# Eurocard_VME_6U_P1.net
KiCad netlist of a schematic drawn in Altium Designer
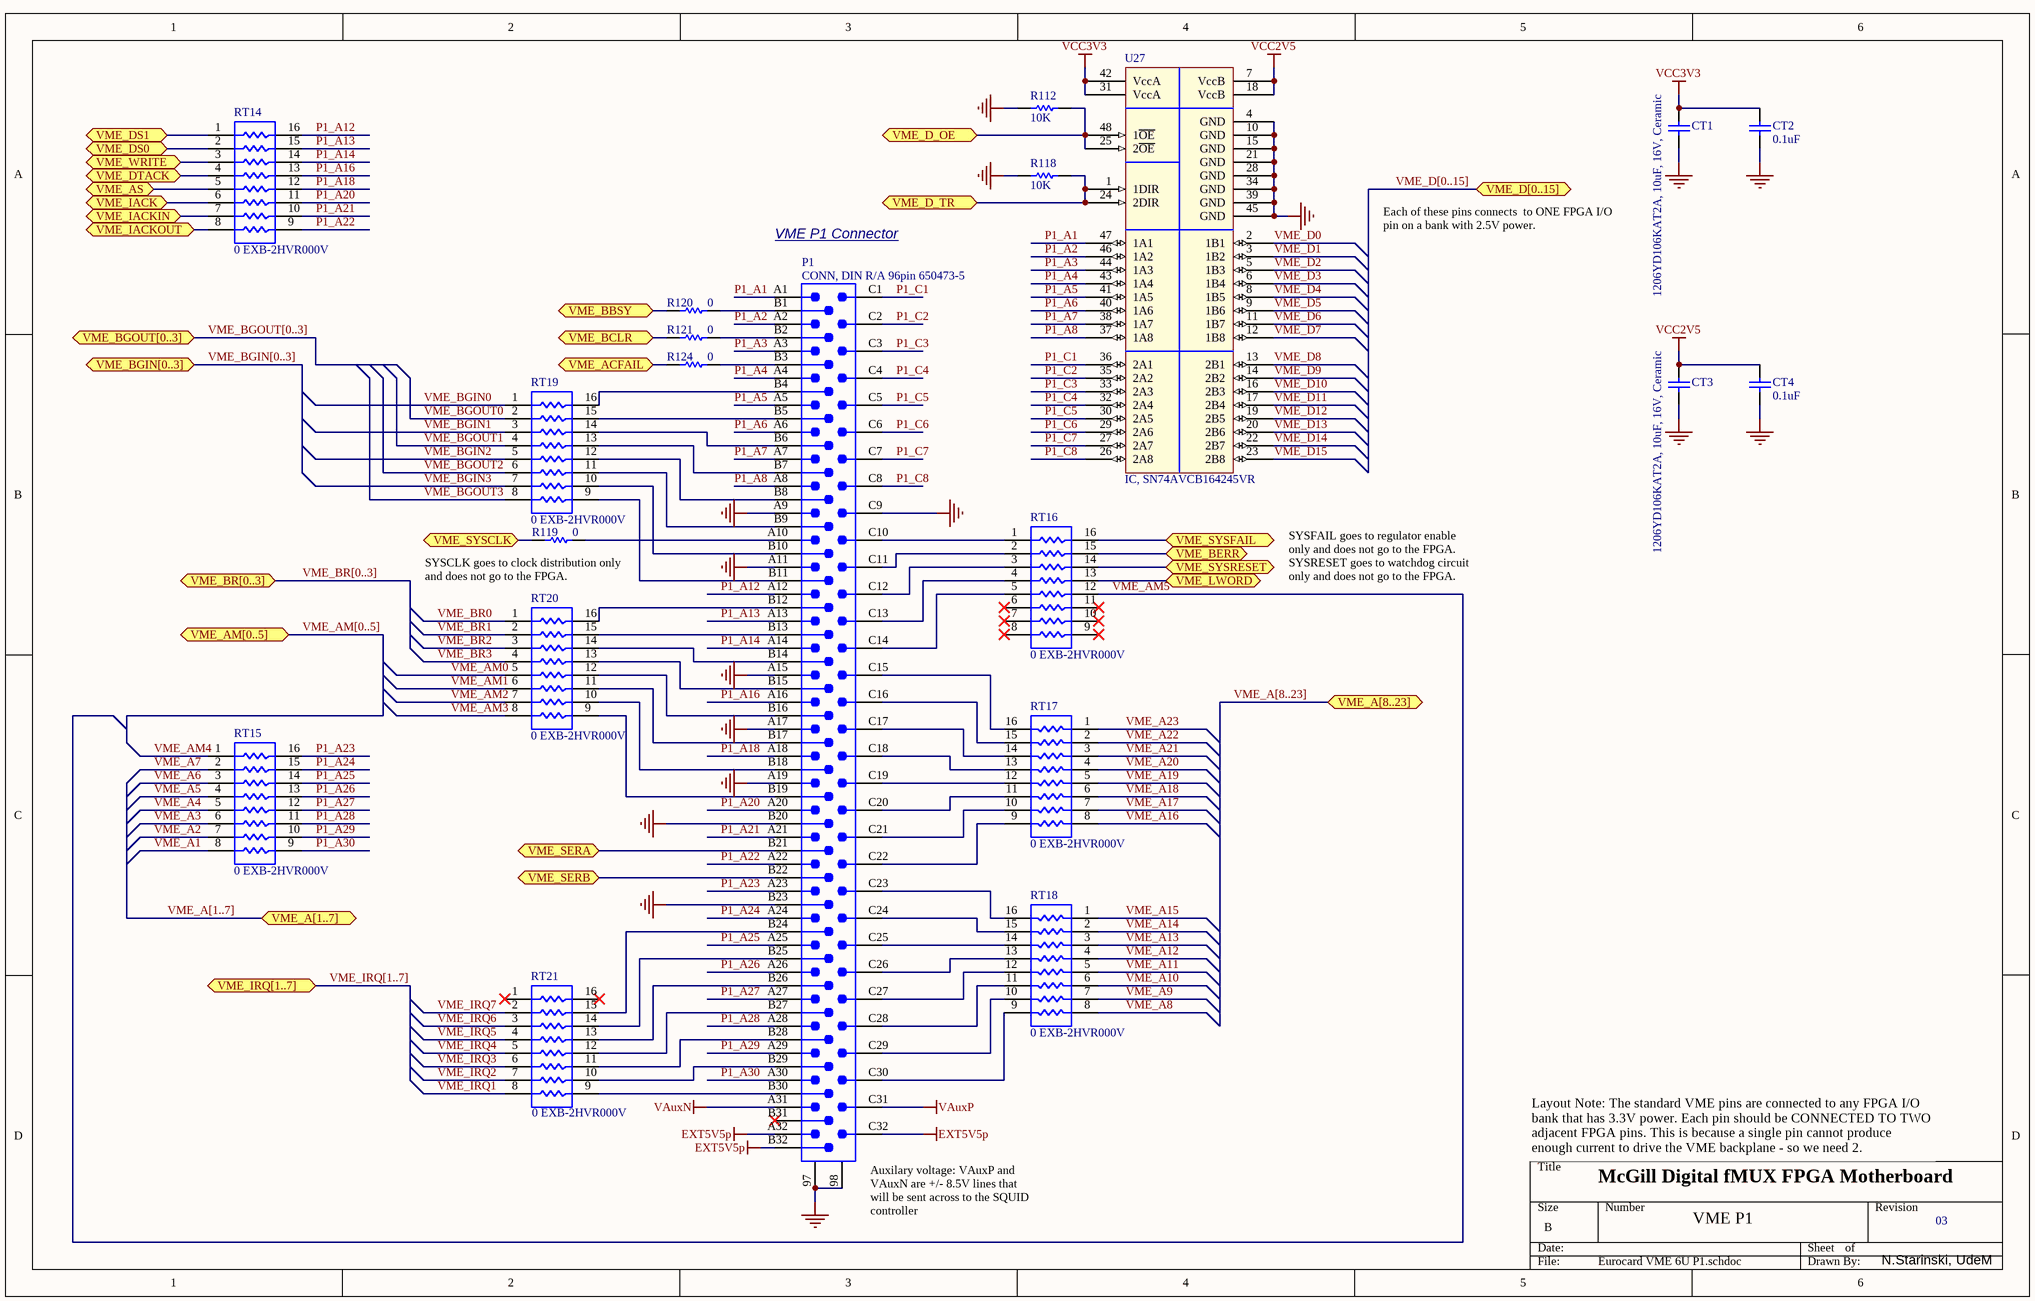
[diagram p0: Eurocard VME 6U P1.schdoc]

(export (version "E")
  (design (tool "Eeschema 10.0.6"))
  (components
    (comp (ref "CT1")
      (value "1206YD106KAT2A, 10uF, 16V, Ceramic")
      (footprint "CC3225-1210")
      (description "CAP POL 1206YD106KAT2A")
      (fields (field (name "PUBLISHER") "Altium Limited"))
      (libsource (lib "Miscellaneous Devices") (part "Cap Semi"))
    )
    (comp (ref "CT2")
      (value "0.1uF")
      (footprint "CC1608-0603")
      (description "Capacitor (Semiconductor SIM Model)")
      (fields (field (name "PUBLISHER") "Altium Limited"))
      (libsource (lib "Miscellaneous Devices") (part "Cap Semi"))
    )
    (comp (ref "CT3")
      (value "1206YD106KAT2A, 10uF, 16V, Ceramic")
      (footprint "CC3225-1210")
      (description "CAP POL 1206YD106KAT2A")
      (fields (field (name "PUBLISHER") "Altium Limited"))
      (libsource (lib "Miscellaneous Devices") (part "Cap Semi"))
    )
    (comp (ref "CT4")
      (value "0.1uF")
      (footprint "CC1608-0603")
      (description "Capacitor (Semiconductor SIM Model)")
      (fields (field (name "PUBLISHER") "Altium Limited"))
      (libsource (lib "Miscellaneous Devices") (part "Cap Semi"))
    )
    (comp (ref "P1")
      (value "CONN, DIN R/A 96pin 650473-5")
      (footprint "CNVME96")
      (description "96-Pin Connector (3x32 2.54mm grid)")
      (libsource (lib "*") (part "CNVME96"))
    )
    (comp (ref "R112")
      (value "10K")
      (footprint "CR1608-0603")
      (description "Resistor 0603")
      (fields (field (name "PUBLISHER") "Altium Limited"))
      (libsource (lib "Miscellaneous Devices") (part "Res Semi"))
    )
    (comp (ref "R118")
      (value "10K")
      (footprint "CR1608-0603")
      (description "Resistor 0603")
      (fields (field (name "PUBLISHER") "Altium Limited"))
      (libsource (lib "Miscellaneous Devices") (part "Res Semi"))
    )
    (comp (ref "R119")
      (value "0")
      (footprint "CR1608-0603")
      (description "Resistor 0603")
      (fields (field (name "PUBLISHER") "Altium Limited"))
      (libsource (lib "Miscellaneous Devices") (part "Res Semi"))
    )
    (comp (ref "R120")
      (value "0")
      (footprint "CR1608-0603")
      (description "Resistor 0603")
      (fields (field (name "PUBLISHER") "Altium Limited"))
      (libsource (lib "Miscellaneous Devices") (part "Res Semi"))
    )
    (comp (ref "R121")
      (value "0")
      (footprint "CR1608-0603")
      (description "Resistor 0603")
      (fields (field (name "PUBLISHER") "Altium Limited"))
      (libsource (lib "Miscellaneous Devices") (part "Res Semi"))
    )
    (comp (ref "R124")
      (value "0")
      (footprint "CR1608-0603")
      (description "Resistor 0603")
      (fields (field (name "PUBLISHER") "Altium Limited"))
      (libsource (lib "Miscellaneous Devices") (part "Res Semi"))
    )
    (comp (ref "RT14")
      (value "0 EXB-2HVR000V")
      (footprint "0402_Array_2HV")
      (description "Isolated Resistor Network")
      (fields (field (name "PUBLISHER") "Altium Limited"))
      (libsource (lib "Miscellaneous Devices 02") (part "Res Pack3"))
    )
    (comp (ref "RT15")
      (value "0 EXB-2HVR000V")
      (footprint "0402_Array_2HV")
      (description "Isolated Resistor Network")
      (fields (field (name "PUBLISHER") "Altium Limited"))
      (libsource (lib "Miscellaneous Devices 02") (part "Res Pack3"))
    )
    (comp (ref "RT16")
      (value "0 EXB-2HVR000V")
      (footprint "0402_Array_2HV")
      (description "Isolated Resistor Network")
      (fields (field (name "PUBLISHER") "Altium Limited"))
      (libsource (lib "Miscellaneous Devices 02") (part "Res Pack3"))
    )
    (comp (ref "RT17")
      (value "0 EXB-2HVR000V")
      (footprint "0402_Array_2HV")
      (description "Isolated Resistor Network")
      (fields (field (name "PUBLISHER") "Altium Limited"))
      (libsource (lib "Miscellaneous Devices 02") (part "Res Pack3"))
    )
    (comp (ref "RT18")
      (value "0 EXB-2HVR000V")
      (description "Isolated Resistor Network")
      (fields (field (name "PUBLISHER") "Altium Limited"))
      (libsource (lib "Miscellaneous Devices 02") (part "Res Pack3"))
    )
    (comp (ref "RT19")
      (value "0 EXB-2HVR000V")
      (footprint "0402_Array_2HV")
      (description "Isolated Resistor Network")
      (fields (field (name "PUBLISHER") "Altium Limited"))
      (libsource (lib "Miscellaneous Devices 02") (part "Res Pack3"))
    )
    (comp (ref "RT20")
      (value "0 EXB-2HVR000V")
      (footprint "0402_Array_2HV")
      (description "Isolated Resistor Network")
      (fields (field (name "PUBLISHER") "Altium Limited"))
      (libsource (lib "Miscellaneous Devices 02") (part "Res Pack3"))
    )
    (comp (ref "RT21")
      (value "0 EXB-2HVR000V")
      (footprint "0402_Array_2HV")
      (description "Isolated Resistor Network")
      (fields (field (name "PUBLISHER") "Altium Limited"))
      (libsource (lib "Miscellaneous Devices 02") (part "Res Pack3"))
    )
    (comp (ref "U27")
      (value "IC, SN74AVCB164245VR")
      (footprint "DGV048")
      (description "16-Bit Dual-Supply Bus Transceiver with CVT and 3-state")
      (libsource (lib "TI Interface Line Transceiver") (part "SN74AVCB164245"))
    )
  )
  (nets
    (net (code "1") (name "/P1_A1") (class "Default")
      (node (ref "P1") (pin "A1") (pinfunction "A1_A1") (pintype "passive"))
      (node (ref "U27") (pin "47") (pinfunction "1A1_47") (pintype "bidirectional"))
    )
    (net (code "2") (name "/P1_A2") (class "Default")
      (node (ref "P1") (pin "A2") (pinfunction "A2_A2") (pintype "passive"))
      (node (ref "U27") (pin "46") (pinfunction "1A2_46") (pintype "bidirectional"))
    )
    (net (code "3") (name "/P1_A3") (class "Default")
      (node (ref "P1") (pin "A3") (pinfunction "A3_A3") (pintype "passive"))
      (node (ref "U27") (pin "44") (pinfunction "1A3_44") (pintype "bidirectional"))
    )
    (net (code "4") (name "/P1_A4") (class "Default")
      (node (ref "P1") (pin "A4") (pinfunction "A4_A4") (pintype "passive"))
      (node (ref "U27") (pin "43") (pinfunction "1A4_43") (pintype "bidirectional"))
    )
    (net (code "5") (name "/P1_A5") (class "Default")
      (node (ref "P1") (pin "A5") (pinfunction "A5_A5") (pintype "passive"))
      (node (ref "U27") (pin "41") (pinfunction "1A5_41") (pintype "bidirectional"))
    )
    (net (code "6") (name "/P1_A6") (class "Default")
      (node (ref "P1") (pin "A6") (pinfunction "A6_A6") (pintype "passive"))
      (node (ref "U27") (pin "40") (pinfunction "1A6_40") (pintype "bidirectional"))
    )
    (net (code "7") (name "/P1_A7") (class "Default")
      (node (ref "P1") (pin "A7") (pinfunction "A7_A7") (pintype "passive"))
      (node (ref "U27") (pin "38") (pinfunction "1A7_38") (pintype "bidirectional"))
    )
    (net (code "8") (name "/P1_A8") (class "Default")
      (node (ref "P1") (pin "A8") (pinfunction "A8_A8") (pintype "passive"))
      (node (ref "U27") (pin "37") (pinfunction "1A8_37") (pintype "bidirectional"))
    )
    (net (code "9") (name "/P1_A12") (class "Default")
      (node (ref "P1") (pin "A12") (pinfunction "A12_A12") (pintype "passive"))
      (node (ref "RT14") (pin "16") (pinfunction "16_16") (pintype "passive"))
    )
    (net (code "10") (name "/P1_A13") (class "Default")
      (node (ref "P1") (pin "A13") (pinfunction "A13_A13") (pintype "passive"))
      (node (ref "RT14") (pin "15") (pinfunction "15_15") (pintype "passive"))
    )
    (net (code "11") (name "/P1_A14") (class "Default")
      (node (ref "P1") (pin "A14") (pinfunction "A14_A14") (pintype "passive"))
      (node (ref "RT14") (pin "14") (pinfunction "14_14") (pintype "passive"))
    )
    (net (code "12") (name "/P1_A16") (class "Default")
      (node (ref "P1") (pin "A16") (pinfunction "A16_A16") (pintype "passive"))
      (node (ref "RT14") (pin "13") (pinfunction "13_13") (pintype "passive"))
    )
    (net (code "13") (name "/P1_A18") (class "Default")
      (node (ref "P1") (pin "A18") (pinfunction "A18_A18") (pintype "passive"))
      (node (ref "RT14") (pin "12") (pinfunction "12_12") (pintype "passive"))
    )
    (net (code "14") (name "/P1_A20") (class "Default")
      (node (ref "P1") (pin "A20") (pinfunction "A20_A20") (pintype "passive"))
      (node (ref "RT14") (pin "11") (pinfunction "11_11") (pintype "passive"))
    )
    (net (code "15") (name "/P1_A21") (class "Default")
      (node (ref "P1") (pin "A21") (pinfunction "A21_A21") (pintype "passive"))
      (node (ref "RT14") (pin "10") (pinfunction "10_10") (pintype "passive"))
    )
    (net (code "16") (name "/P1_A22") (class "Default")
      (node (ref "P1") (pin "A22") (pinfunction "A22_A22") (pintype "passive"))
      (node (ref "RT14") (pin "9") (pinfunction "9_9") (pintype "passive"))
    )
    (net (code "17") (name "/P1_A23") (class "Default")
      (node (ref "P1") (pin "A23") (pinfunction "A23_A23") (pintype "passive"))
      (node (ref "RT15") (pin "16") (pinfunction "16_16") (pintype "passive"))
    )
    (net (code "18") (name "/P1_A24") (class "Default")
      (node (ref "P1") (pin "A24") (pinfunction "A24_A24") (pintype "passive"))
      (node (ref "RT15") (pin "15") (pinfunction "15_15") (pintype "passive"))
    )
    (net (code "19") (name "/P1_A25") (class "Default")
      (node (ref "P1") (pin "A25") (pinfunction "A25_A25") (pintype "passive"))
      (node (ref "RT15") (pin "14") (pinfunction "14_14") (pintype "passive"))
    )
    (net (code "20") (name "/P1_A26") (class "Default")
      (node (ref "P1") (pin "A26") (pinfunction "A26_A26") (pintype "passive"))
      (node (ref "RT15") (pin "13") (pinfunction "13_13") (pintype "passive"))
    )
    (net (code "21") (name "/P1_A27") (class "Default")
      (node (ref "P1") (pin "A27") (pinfunction "A27_A27") (pintype "passive"))
      (node (ref "RT15") (pin "12") (pinfunction "12_12") (pintype "passive"))
    )
    (net (code "22") (name "/P1_A28") (class "Default")
      (node (ref "P1") (pin "A28") (pinfunction "A28_A28") (pintype "passive"))
      (node (ref "RT15") (pin "11") (pinfunction "11_11") (pintype "passive"))
    )
    (net (code "23") (name "/P1_A29") (class "Default")
      (node (ref "P1") (pin "A29") (pinfunction "A29_A29") (pintype "passive"))
      (node (ref "RT15") (pin "10") (pinfunction "10_10") (pintype "passive"))
    )
    (net (code "24") (name "/P1_A30") (class "Default")
      (node (ref "P1") (pin "A30") (pinfunction "A30_A30") (pintype "passive"))
      (node (ref "RT15") (pin "9") (pinfunction "9_9") (pintype "passive"))
    )
    (net (code "25") (name "/P1_C1") (class "Default")
      (node (ref "P1") (pin "C1") (pinfunction "C1_C1") (pintype "passive"))
      (node (ref "U27") (pin "36") (pinfunction "2A1_36") (pintype "bidirectional"))
    )
    (net (code "26") (name "/P1_C2") (class "Default")
      (node (ref "P1") (pin "C2") (pinfunction "C2_C2") (pintype "passive"))
      (node (ref "U27") (pin "35") (pinfunction "2A2_35") (pintype "bidirectional"))
    )
    (net (code "27") (name "/P1_C3") (class "Default")
      (node (ref "P1") (pin "C3") (pinfunction "C3_C3") (pintype "passive"))
      (node (ref "U27") (pin "33") (pinfunction "2A3_33") (pintype "bidirectional"))
    )
    (net (code "28") (name "/P1_C4") (class "Default")
      (node (ref "P1") (pin "C4") (pinfunction "C4_C4") (pintype "passive"))
      (node (ref "U27") (pin "32") (pinfunction "2A4_32") (pintype "bidirectional"))
    )
    (net (code "29") (name "/P1_C5") (class "Default")
      (node (ref "P1") (pin "C5") (pinfunction "C5_C5") (pintype "passive"))
      (node (ref "U27") (pin "30") (pinfunction "2A5_30") (pintype "bidirectional"))
    )
    (net (code "30") (name "/P1_C6") (class "Default")
      (node (ref "P1") (pin "C6") (pinfunction "C6_C6") (pintype "passive"))
      (node (ref "U27") (pin "29") (pinfunction "2A6_29") (pintype "bidirectional"))
    )
    (net (code "31") (name "/P1_C7") (class "Default")
      (node (ref "P1") (pin "C7") (pinfunction "C7_C7") (pintype "passive"))
      (node (ref "U27") (pin "27") (pinfunction "2A7_27") (pintype "bidirectional"))
    )
    (net (code "32") (name "/P1_C8") (class "Default")
      (node (ref "P1") (pin "C8") (pinfunction "C8_C8") (pintype "passive"))
      (node (ref "U27") (pin "26") (pinfunction "2A8_26") (pintype "bidirectional"))
    )
    (net (code "33") (name "/VME_A1") (class "Default")
      (node (ref "RT15") (pin "8") (pinfunction "8_8") (pintype "passive"))
    )
    (net (code "34") (name "/VME_A2") (class "Default")
      (node (ref "RT15") (pin "7") (pinfunction "7_7") (pintype "passive"))
    )
    (net (code "35") (name "/VME_A3") (class "Default")
      (node (ref "RT15") (pin "6") (pinfunction "6_6") (pintype "passive"))
    )
    (net (code "36") (name "/VME_A4") (class "Default")
      (node (ref "RT15") (pin "5") (pinfunction "5_5") (pintype "passive"))
    )
    (net (code "37") (name "/VME_A5") (class "Default")
      (node (ref "RT15") (pin "4") (pinfunction "4_4") (pintype "passive"))
    )
    (net (code "38") (name "/VME_A6") (class "Default")
      (node (ref "RT15") (pin "3") (pinfunction "3_3") (pintype "passive"))
    )
    (net (code "39") (name "/VME_A7") (class "Default")
      (node (ref "RT15") (pin "2") (pinfunction "2_2") (pintype "passive"))
    )
    (net (code "40") (name "/VME_A8") (class "Default")
      (node (ref "RT18") (pin "8") (pinfunction "8_8") (pintype "passive"))
    )
    (net (code "41") (name "/VME_A9") (class "Default")
      (node (ref "RT18") (pin "7") (pinfunction "7_7") (pintype "passive"))
    )
    (net (code "42") (name "/VME_A10") (class "Default")
      (node (ref "RT18") (pin "6") (pinfunction "6_6") (pintype "passive"))
    )
    (net (code "43") (name "/VME_A11") (class "Default")
      (node (ref "RT18") (pin "5") (pinfunction "5_5") (pintype "passive"))
    )
    (net (code "44") (name "/VME_A12") (class "Default")
      (node (ref "RT18") (pin "4") (pinfunction "4_4") (pintype "passive"))
    )
    (net (code "45") (name "/VME_A13") (class "Default")
      (node (ref "RT18") (pin "3") (pinfunction "3_3") (pintype "passive"))
    )
    (net (code "46") (name "/VME_A14") (class "Default")
      (node (ref "RT18") (pin "2") (pinfunction "2_2") (pintype "passive"))
    )
    (net (code "47") (name "/VME_A15") (class "Default")
      (node (ref "RT18") (pin "1") (pinfunction "1_1") (pintype "passive"))
    )
    (net (code "48") (name "/VME_A16") (class "Default")
      (node (ref "RT17") (pin "8") (pinfunction "8_8") (pintype "passive"))
    )
    (net (code "49") (name "/VME_A17") (class "Default")
      (node (ref "RT17") (pin "7") (pinfunction "7_7") (pintype "passive"))
    )
    (net (code "50") (name "/VME_A18") (class "Default")
      (node (ref "RT17") (pin "6") (pinfunction "6_6") (pintype "passive"))
    )
    (net (code "51") (name "/VME_A19") (class "Default")
      (node (ref "RT17") (pin "5") (pinfunction "5_5") (pintype "passive"))
    )
    (net (code "52") (name "/VME_A20") (class "Default")
      (node (ref "RT17") (pin "4") (pinfunction "4_4") (pintype "passive"))
    )
    (net (code "53") (name "/VME_A21") (class "Default")
      (node (ref "RT17") (pin "3") (pinfunction "3_3") (pintype "passive"))
    )
    (net (code "54") (name "/VME_A22") (class "Default")
      (node (ref "RT17") (pin "2") (pinfunction "2_2") (pintype "passive"))
    )
    (net (code "55") (name "/VME_A23") (class "Default")
      (node (ref "RT17") (pin "1") (pinfunction "1_1") (pintype "passive"))
    )
    (net (code "56") (name "/VME_ACFAIL") (class "Default")
      (node (ref "R124") (pin "1") (pinfunction "1_1") (pintype "passive"))
    )
    (net (code "57") (name "/VME_AM0") (class "Default")
      (node (ref "RT20") (pin "5") (pinfunction "5_5") (pintype "passive"))
    )
    (net (code "58") (name "/VME_AM1") (class "Default")
      (node (ref "RT20") (pin "6") (pinfunction "6_6") (pintype "passive"))
    )
    (net (code "59") (name "/VME_AM2") (class "Default")
      (node (ref "RT20") (pin "7") (pinfunction "7_7") (pintype "passive"))
    )
    (net (code "60") (name "/VME_AM3") (class "Default")
      (node (ref "RT20") (pin "8") (pinfunction "8_8") (pintype "passive"))
    )
    (net (code "61") (name "/VME_AM4") (class "Default")
      (node (ref "RT15") (pin "1") (pinfunction "1_1") (pintype "passive"))
    )
    (net (code "62") (name "/VME_AM5") (class "Default")
      (node (ref "RT16") (pin "12") (pinfunction "12_12") (pintype "passive"))
    )
    (net (code "64") (name "/VME_AS") (class "Default")
      (node (ref "RT14") (pin "5") (pinfunction "5_5") (pintype "passive"))
    )
    (net (code "67") (name "/VME_BBSY") (class "Default")
      (node (ref "R120") (pin "1") (pinfunction "1_1") (pintype "passive"))
    )
    (net (code "68") (name "/VME_BCLR") (class "Default")
      (node (ref "R121") (pin "1") (pinfunction "1_1") (pintype "passive"))
    )
    (net (code "69") (name "/VME_BERR") (class "Default")
      (node (ref "RT16") (pin "15") (pinfunction "15_15") (pintype "passive"))
    )
    (net (code "70") (name "/VME_BGIN0") (class "Default")
      (node (ref "RT19") (pin "1") (pinfunction "1_1") (pintype "passive"))
    )
    (net (code "71") (name "/VME_BGIN1") (class "Default")
      (node (ref "RT19") (pin "3") (pinfunction "3_3") (pintype "passive"))
    )
    (net (code "72") (name "/VME_BGIN2") (class "Default")
      (node (ref "RT19") (pin "5") (pinfunction "5_5") (pintype "passive"))
    )
    (net (code "73") (name "/VME_BGIN3") (class "Default")
      (node (ref "RT19") (pin "7") (pinfunction "7_7") (pintype "passive"))
    )
    (net (code "75") (name "/VME_BGOUT0") (class "Default")
      (node (ref "RT19") (pin "2") (pinfunction "2_2") (pintype "passive"))
    )
    (net (code "76") (name "/VME_BGOUT1") (class "Default")
      (node (ref "RT19") (pin "4") (pinfunction "4_4") (pintype "passive"))
    )
    (net (code "77") (name "/VME_BGOUT2") (class "Default")
      (node (ref "RT19") (pin "6") (pinfunction "6_6") (pintype "passive"))
    )
    (net (code "78") (name "/VME_BGOUT3") (class "Default")
      (node (ref "RT19") (pin "8") (pinfunction "8_8") (pintype "passive"))
    )
    (net (code "80") (name "/VME_BR0") (class "Default")
      (node (ref "RT20") (pin "1") (pinfunction "1_1") (pintype "passive"))
    )
    (net (code "81") (name "/VME_BR1") (class "Default")
      (node (ref "RT20") (pin "2") (pinfunction "2_2") (pintype "passive"))
    )
    (net (code "82") (name "/VME_BR2") (class "Default")
      (node (ref "RT20") (pin "3") (pinfunction "3_3") (pintype "passive"))
    )
    (net (code "83") (name "/VME_BR3") (class "Default")
      (node (ref "RT20") (pin "4") (pinfunction "4_4") (pintype "passive"))
    )
    (net (code "85") (name "/VME_D0") (class "Default")
      (node (ref "U27") (pin "2") (pinfunction "1B1_2") (pintype "bidirectional"))
    )
    (net (code "86") (name "/VME_D1") (class "Default")
      (node (ref "U27") (pin "3") (pinfunction "1B2_3") (pintype "bidirectional"))
    )
    (net (code "87") (name "/VME_D2") (class "Default")
      (node (ref "U27") (pin "5") (pinfunction "1B3_5") (pintype "bidirectional"))
    )
    (net (code "88") (name "/VME_D3") (class "Default")
      (node (ref "U27") (pin "6") (pinfunction "1B4_6") (pintype "bidirectional"))
    )
    (net (code "89") (name "/VME_D4") (class "Default")
      (node (ref "U27") (pin "8") (pinfunction "1B5_8") (pintype "bidirectional"))
    )
    (net (code "90") (name "/VME_D5") (class "Default")
      (node (ref "U27") (pin "9") (pinfunction "1B6_9") (pintype "bidirectional"))
    )
    (net (code "91") (name "/VME_D6") (class "Default")
      (node (ref "U27") (pin "11") (pinfunction "1B7_11") (pintype "bidirectional"))
    )
    (net (code "92") (name "/VME_D7") (class "Default")
      (node (ref "U27") (pin "12") (pinfunction "1B8_12") (pintype "bidirectional"))
    )
    (net (code "93") (name "/VME_D8") (class "Default")
      (node (ref "U27") (pin "13") (pinfunction "2B1_13") (pintype "bidirectional"))
    )
    (net (code "94") (name "/VME_D9") (class "Default")
      (node (ref "U27") (pin "14") (pinfunction "2B2_14") (pintype "bidirectional"))
    )
    (net (code "95") (name "/VME_D10") (class "Default")
      (node (ref "U27") (pin "16") (pinfunction "2B3_16") (pintype "bidirectional"))
    )
    (net (code "96") (name "/VME_D11") (class "Default")
      (node (ref "U27") (pin "17") (pinfunction "2B4_17") (pintype "bidirectional"))
    )
    (net (code "97") (name "/VME_D12") (class "Default")
      (node (ref "U27") (pin "19") (pinfunction "2B5_19") (pintype "bidirectional"))
    )
    (net (code "98") (name "/VME_D13") (class "Default")
      (node (ref "U27") (pin "20") (pinfunction "2B6_20") (pintype "bidirectional"))
    )
    (net (code "99") (name "/VME_D14") (class "Default")
      (node (ref "U27") (pin "22") (pinfunction "2B7_22") (pintype "bidirectional"))
    )
    (net (code "100") (name "/VME_D15") (class "Default")
      (node (ref "U27") (pin "23") (pinfunction "2B8_23") (pintype "bidirectional"))
    )
    (net (code "101") (name "/VME_DS0") (class "Default")
      (node (ref "RT14") (pin "2") (pinfunction "2_2") (pintype "passive"))
    )
    (net (code "102") (name "/VME_DS1") (class "Default")
      (node (ref "RT14") (pin "1") (pinfunction "1_1") (pintype "passive"))
    )
    (net (code "103") (name "/VME_DTACK") (class "Default")
      (node (ref "RT14") (pin "4") (pinfunction "4_4") (pintype "passive"))
    )
    (net (code "105") (name "/VME_D_OE") (class "Default")
      (node (ref "R112") (pin "2") (pinfunction "2_2") (pintype "passive"))
      (node (ref "U27") (pin "25") (pinfunction "2~{OE}_25") (pintype "input"))
      (node (ref "U27") (pin "48") (pinfunction "1~{OE}_48") (pintype "input"))
    )
    (net (code "106") (name "/VME_D_TR") (class "Default")
      (node (ref "R118") (pin "2") (pinfunction "2_2") (pintype "passive"))
      (node (ref "U27") (pin "1") (pinfunction "1DIR_1") (pintype "input"))
      (node (ref "U27") (pin "24") (pinfunction "2DIR_24") (pintype "input"))
    )
    (net (code "107") (name "/VME_IACK") (class "Default")
      (node (ref "RT14") (pin "6") (pinfunction "6_6") (pintype "passive"))
    )
    (net (code "108") (name "/VME_IACKIN") (class "Default")
      (node (ref "RT14") (pin "7") (pinfunction "7_7") (pintype "passive"))
    )
    (net (code "109") (name "/VME_IACKOUT") (class "Default")
      (node (ref "RT14") (pin "8") (pinfunction "8_8") (pintype "passive"))
    )
    (net (code "110") (name "/VME_IRQ1") (class "Default")
      (node (ref "RT21") (pin "8") (pinfunction "8_8") (pintype "passive"))
    )
    (net (code "111") (name "/VME_IRQ2") (class "Default")
      (node (ref "RT21") (pin "7") (pinfunction "7_7") (pintype "passive"))
    )
    (net (code "112") (name "/VME_IRQ3") (class "Default")
      (node (ref "RT21") (pin "6") (pinfunction "6_6") (pintype "passive"))
    )
    (net (code "113") (name "/VME_IRQ4") (class "Default")
      (node (ref "RT21") (pin "5") (pinfunction "5_5") (pintype "passive"))
    )
    (net (code "114") (name "/VME_IRQ5") (class "Default")
      (node (ref "RT21") (pin "4") (pinfunction "4_4") (pintype "passive"))
    )
    (net (code "115") (name "/VME_IRQ6") (class "Default")
      (node (ref "RT21") (pin "3") (pinfunction "3_3") (pintype "passive"))
    )
    (net (code "116") (name "/VME_IRQ7") (class "Default")
      (node (ref "RT21") (pin "2") (pinfunction "2_2") (pintype "passive"))
    )
    (net (code "118") (name "/VME_LWORD") (class "Default")
      (node (ref "RT16") (pin "13") (pinfunction "13_13") (pintype "passive"))
    )
    (net (code "119") (name "/VME_SERA") (class "Default")
      (node (ref "P1") (pin "B21") (pinfunction "B21_B21") (pintype "passive"))
    )
    (net (code "120") (name "/VME_SERB") (class "Default")
      (node (ref "P1") (pin "B22") (pinfunction "B22_B22") (pintype "passive"))
    )
    (net (code "121") (name "/VME_SYSCLK") (class "Default")
      (node (ref "R119") (pin "1") (pinfunction "1_1") (pintype "passive"))
    )
    (net (code "122") (name "/VME_SYSFAIL") (class "Default")
      (node (ref "RT16") (pin "16") (pinfunction "16_16") (pintype "passive"))
    )
    (net (code "123") (name "/VME_SYSRESET") (class "Default")
      (node (ref "RT16") (pin "14") (pinfunction "14_14") (pintype "passive"))
    )
    (net (code "124") (name "/VME_WRITE") (class "Default")
      (node (ref "RT14") (pin "3") (pinfunction "3_3") (pintype "passive"))
    )
    (net (code "125") (name "EXT5V5p") (class "Default")
      (node (ref "P1") (pin "A32") (pinfunction "A32_A32") (pintype "passive"))
      (node (ref "P1") (pin "B32") (pinfunction "B32_B32") (pintype "passive"))
      (node (ref "P1") (pin "C32") (pinfunction "C32_C32") (pintype "passive"))
    )
    (net (code "126") (name "GND") (class "Default")
      (node (ref "CT1") (pin "2") (pinfunction "2_2") (pintype "passive"))
      (node (ref "CT2") (pin "2") (pinfunction "2_2") (pintype "passive"))
      (node (ref "CT3") (pin "2") (pinfunction "2_2") (pintype "passive"))
      (node (ref "CT4") (pin "2") (pinfunction "2_2") (pintype "passive"))
      (node (ref "P1") (pin "97") (pinfunction "97_97") (pintype "passive"))
      (node (ref "P1") (pin "98") (pinfunction "98_98") (pintype "passive"))
      (node (ref "P1") (pin "A11") (pinfunction "A11_A11") (pintype "passive"))
      (node (ref "P1") (pin "A15") (pinfunction "A15_A15") (pintype "passive"))
      (node (ref "P1") (pin "A17") (pinfunction "A17_A17") (pintype "passive"))
      (node (ref "P1") (pin "A19") (pinfunction "A19_A19") (pintype "passive"))
      (node (ref "P1") (pin "A9") (pinfunction "A9_A9") (pintype "passive"))
      (node (ref "P1") (pin "B20") (pinfunction "B20_B20") (pintype "passive"))
      (node (ref "P1") (pin "B23") (pinfunction "B23_B23") (pintype "passive"))
      (node (ref "P1") (pin "C9") (pinfunction "C9_C9") (pintype "passive"))
      (node (ref "R112") (pin "1") (pinfunction "1_1") (pintype "passive"))
      (node (ref "R118") (pin "1") (pinfunction "1_1") (pintype "passive"))
      (node (ref "U27") (pin "10") (pinfunction "GND_10") (pintype "power_in"))
      (node (ref "U27") (pin "15") (pinfunction "GND_15") (pintype "power_in"))
      (node (ref "U27") (pin "21") (pinfunction "GND_21") (pintype "power_in"))
      (node (ref "U27") (pin "28") (pinfunction "GND_28") (pintype "power_in"))
      (node (ref "U27") (pin "34") (pinfunction "GND_34") (pintype "power_in"))
      (node (ref "U27") (pin "39") (pinfunction "GND_39") (pintype "power_in"))
      (node (ref "U27") (pin "4") (pinfunction "GND_4") (pintype "power_in"))
      (node (ref "U27") (pin "45") (pinfunction "GND_45") (pintype "power_in"))
    )
    (net (code "127") (name "Net-(P1-PadA10)") (class "Default")
      (node (ref "P1") (pin "A10") (pinfunction "A10_A10") (pintype "passive"))
      (node (ref "R119") (pin "2") (pinfunction "2_2") (pintype "passive"))
    )
    (net (code "128") (name "Net-(P1-PadB1)") (class "Default")
      (node (ref "P1") (pin "B1") (pinfunction "B1_B1") (pintype "passive"))
      (node (ref "R120") (pin "2") (pinfunction "2_2") (pintype "passive"))
    )
    (net (code "129") (name "Net-(P1-PadB2)") (class "Default")
      (node (ref "P1") (pin "B2") (pinfunction "B2_B2") (pintype "passive"))
      (node (ref "R121") (pin "2") (pinfunction "2_2") (pintype "passive"))
    )
    (net (code "130") (name "Net-(P1-PadB3)") (class "Default")
      (node (ref "P1") (pin "B3") (pinfunction "B3_B3") (pintype "passive"))
      (node (ref "R124") (pin "2") (pinfunction "2_2") (pintype "passive"))
    )
    (net (code "131") (name "Net-(P1-PadB4)") (class "Default")
      (node (ref "P1") (pin "B4") (pinfunction "B4_B4") (pintype "passive"))
      (node (ref "RT19") (pin "16") (pinfunction "16_16") (pintype "passive"))
    )
    (net (code "132") (name "Net-(P1-PadB5)") (class "Default")
      (node (ref "P1") (pin "B5") (pinfunction "B5_B5") (pintype "passive"))
      (node (ref "RT19") (pin "15") (pinfunction "15_15") (pintype "passive"))
    )
    (net (code "133") (name "Net-(P1-PadB6)") (class "Default")
      (node (ref "P1") (pin "B6") (pinfunction "B6_B6") (pintype "passive"))
      (node (ref "RT19") (pin "14") (pinfunction "14_14") (pintype "passive"))
    )
    (net (code "134") (name "Net-(P1-PadB7)") (class "Default")
      (node (ref "P1") (pin "B7") (pinfunction "B7_B7") (pintype "passive"))
      (node (ref "RT19") (pin "13") (pinfunction "13_13") (pintype "passive"))
    )
    (net (code "135") (name "Net-(P1-PadB8)") (class "Default")
      (node (ref "P1") (pin "B8") (pinfunction "B8_B8") (pintype "passive"))
      (node (ref "RT19") (pin "12") (pinfunction "12_12") (pintype "passive"))
    )
    (net (code "136") (name "Net-(P1-PadB9)") (class "Default")
      (node (ref "P1") (pin "B9") (pinfunction "B9_B9") (pintype "passive"))
      (node (ref "RT19") (pin "11") (pinfunction "11_11") (pintype "passive"))
    )
    (net (code "137") (name "Net-(P1-PadB10)") (class "Default")
      (node (ref "P1") (pin "B10") (pinfunction "B10_B10") (pintype "passive"))
      (node (ref "RT19") (pin "10") (pinfunction "10_10") (pintype "passive"))
    )
    (net (code "138") (name "Net-(P1-PadB11)") (class "Default")
      (node (ref "P1") (pin "B11") (pinfunction "B11_B11") (pintype "passive"))
      (node (ref "RT19") (pin "9") (pinfunction "9_9") (pintype "passive"))
    )
    (net (code "139") (name "Net-(P1-PadB12)") (class "Default")
      (node (ref "P1") (pin "B12") (pinfunction "B12_B12") (pintype "passive"))
      (node (ref "RT20") (pin "16") (pinfunction "16_16") (pintype "passive"))
    )
    (net (code "140") (name "Net-(P1-PadB13)") (class "Default")
      (node (ref "P1") (pin "B13") (pinfunction "B13_B13") (pintype "passive"))
      (node (ref "RT20") (pin "15") (pinfunction "15_15") (pintype "passive"))
    )
    (net (code "141") (name "Net-(P1-PadB14)") (class "Default")
      (node (ref "P1") (pin "B14") (pinfunction "B14_B14") (pintype "passive"))
      (node (ref "RT20") (pin "14") (pinfunction "14_14") (pintype "passive"))
    )
    (net (code "142") (name "Net-(P1-PadB15)") (class "Default")
      (node (ref "P1") (pin "B15") (pinfunction "B15_B15") (pintype "passive"))
      (node (ref "RT20") (pin "13") (pinfunction "13_13") (pintype "passive"))
    )
    (net (code "143") (name "Net-(P1-PadB16)") (class "Default")
      (node (ref "P1") (pin "B16") (pinfunction "B16_B16") (pintype "passive"))
      (node (ref "RT20") (pin "12") (pinfunction "12_12") (pintype "passive"))
    )
    (net (code "144") (name "Net-(P1-PadB17)") (class "Default")
      (node (ref "P1") (pin "B17") (pinfunction "B17_B17") (pintype "passive"))
      (node (ref "RT20") (pin "11") (pinfunction "11_11") (pintype "passive"))
    )
    (net (code "145") (name "Net-(P1-PadB18)") (class "Default")
      (node (ref "P1") (pin "B18") (pinfunction "B18_B18") (pintype "passive"))
      (node (ref "RT20") (pin "10") (pinfunction "10_10") (pintype "passive"))
    )
    (net (code "146") (name "Net-(P1-PadB19)") (class "Default")
      (node (ref "P1") (pin "B19") (pinfunction "B19_B19") (pintype "passive"))
      (node (ref "RT20") (pin "9") (pinfunction "9_9") (pintype "passive"))
    )
    (net (code "147") (name "Net-(P1-PadB24)") (class "Default")
      (node (ref "P1") (pin "B24") (pinfunction "B24_B24") (pintype "passive"))
      (node (ref "RT21") (pin "15") (pinfunction "15_15") (pintype "passive"))
    )
    (net (code "148") (name "Net-(P1-PadB25)") (class "Default")
      (node (ref "P1") (pin "B25") (pinfunction "B25_B25") (pintype "passive"))
      (node (ref "RT21") (pin "14") (pinfunction "14_14") (pintype "passive"))
    )
    (net (code "149") (name "Net-(P1-PadB26)") (class "Default")
      (node (ref "P1") (pin "B26") (pinfunction "B26_B26") (pintype "passive"))
      (node (ref "RT21") (pin "13") (pinfunction "13_13") (pintype "passive"))
    )
    (net (code "150") (name "Net-(P1-PadB27)") (class "Default")
      (node (ref "P1") (pin "B27") (pinfunction "B27_B27") (pintype "passive"))
      (node (ref "RT21") (pin "12") (pinfunction "12_12") (pintype "passive"))
    )
    (net (code "151") (name "Net-(P1-PadB28)") (class "Default")
      (node (ref "P1") (pin "B28") (pinfunction "B28_B28") (pintype "passive"))
      (node (ref "RT21") (pin "11") (pinfunction "11_11") (pintype "passive"))
    )
    (net (code "152") (name "Net-(P1-PadB29)") (class "Default")
      (node (ref "P1") (pin "B29") (pinfunction "B29_B29") (pintype "passive"))
      (node (ref "RT21") (pin "10") (pinfunction "10_10") (pintype "passive"))
    )
    (net (code "153") (name "Net-(P1-PadB30)") (class "Default")
      (node (ref "P1") (pin "B30") (pinfunction "B30_B30") (pintype "passive"))
      (node (ref "RT21") (pin "9") (pinfunction "9_9") (pintype "passive"))
    )
    (net (code "154") (name "Net-(P1-PadC10)") (class "Default")
      (node (ref "P1") (pin "C10") (pinfunction "C10_C10") (pintype "passive"))
      (node (ref "RT16") (pin "1") (pinfunction "1_1") (pintype "passive"))
    )
    (net (code "155") (name "Net-(P1-PadC11)") (class "Default")
      (node (ref "P1") (pin "C11") (pinfunction "C11_C11") (pintype "passive"))
      (node (ref "RT16") (pin "2") (pinfunction "2_2") (pintype "passive"))
    )
    (net (code "156") (name "Net-(P1-PadC12)") (class "Default")
      (node (ref "P1") (pin "C12") (pinfunction "C12_C12") (pintype "passive"))
      (node (ref "RT16") (pin "3") (pinfunction "3_3") (pintype "passive"))
    )
    (net (code "157") (name "Net-(P1-PadC13)") (class "Default")
      (node (ref "P1") (pin "C13") (pinfunction "C13_C13") (pintype "passive"))
      (node (ref "RT16") (pin "4") (pinfunction "4_4") (pintype "passive"))
    )
    (net (code "158") (name "Net-(P1-PadC14)") (class "Default")
      (node (ref "P1") (pin "C14") (pinfunction "C14_C14") (pintype "passive"))
      (node (ref "RT16") (pin "5") (pinfunction "5_5") (pintype "passive"))
    )
    (net (code "159") (name "Net-(P1-PadC15)") (class "Default")
      (node (ref "P1") (pin "C15") (pinfunction "C15_C15") (pintype "passive"))
      (node (ref "RT17") (pin "16") (pinfunction "16_16") (pintype "passive"))
    )
    (net (code "160") (name "Net-(P1-PadC16)") (class "Default")
      (node (ref "P1") (pin "C16") (pinfunction "C16_C16") (pintype "passive"))
      (node (ref "RT17") (pin "15") (pinfunction "15_15") (pintype "passive"))
    )
    (net (code "161") (name "Net-(P1-PadC17)") (class "Default")
      (node (ref "P1") (pin "C17") (pinfunction "C17_C17") (pintype "passive"))
      (node (ref "RT17") (pin "14") (pinfunction "14_14") (pintype "passive"))
    )
    (net (code "162") (name "Net-(P1-PadC18)") (class "Default")
      (node (ref "P1") (pin "C18") (pinfunction "C18_C18") (pintype "passive"))
      (node (ref "RT17") (pin "13") (pinfunction "13_13") (pintype "passive"))
    )
    (net (code "163") (name "Net-(P1-PadC19)") (class "Default")
      (node (ref "P1") (pin "C19") (pinfunction "C19_C19") (pintype "passive"))
      (node (ref "RT17") (pin "12") (pinfunction "12_12") (pintype "passive"))
    )
    (net (code "164") (name "Net-(P1-PadC20)") (class "Default")
      (node (ref "P1") (pin "C20") (pinfunction "C20_C20") (pintype "passive"))
      (node (ref "RT17") (pin "11") (pinfunction "11_11") (pintype "passive"))
    )
    (net (code "165") (name "Net-(P1-PadC21)") (class "Default")
      (node (ref "P1") (pin "C21") (pinfunction "C21_C21") (pintype "passive"))
      (node (ref "RT17") (pin "10") (pinfunction "10_10") (pintype "passive"))
    )
    (net (code "166") (name "Net-(P1-PadC22)") (class "Default")
      (node (ref "P1") (pin "C22") (pinfunction "C22_C22") (pintype "passive"))
      (node (ref "RT17") (pin "9") (pinfunction "9_9") (pintype "passive"))
    )
    (net (code "167") (name "Net-(P1-PadC23)") (class "Default")
      (node (ref "P1") (pin "C23") (pinfunction "C23_C23") (pintype "passive"))
      (node (ref "RT18") (pin "16") (pinfunction "16_16") (pintype "passive"))
    )
    (net (code "168") (name "Net-(P1-PadC24)") (class "Default")
      (node (ref "P1") (pin "C24") (pinfunction "C24_C24") (pintype "passive"))
      (node (ref "RT18") (pin "15") (pinfunction "15_15") (pintype "passive"))
    )
    (net (code "169") (name "Net-(P1-PadC25)") (class "Default")
      (node (ref "P1") (pin "C25") (pinfunction "C25_C25") (pintype "passive"))
      (node (ref "RT18") (pin "14") (pinfunction "14_14") (pintype "passive"))
    )
    (net (code "170") (name "Net-(P1-PadC26)") (class "Default")
      (node (ref "P1") (pin "C26") (pinfunction "C26_C26") (pintype "passive"))
      (node (ref "RT18") (pin "13") (pinfunction "13_13") (pintype "passive"))
    )
    (net (code "171") (name "Net-(P1-PadC27)") (class "Default")
      (node (ref "P1") (pin "C27") (pinfunction "C27_C27") (pintype "passive"))
      (node (ref "RT18") (pin "12") (pinfunction "12_12") (pintype "passive"))
    )
    (net (code "172") (name "Net-(P1-PadC28)") (class "Default")
      (node (ref "P1") (pin "C28") (pinfunction "C28_C28") (pintype "passive"))
      (node (ref "RT18") (pin "11") (pinfunction "11_11") (pintype "passive"))
    )
    (net (code "173") (name "Net-(P1-PadC29)") (class "Default")
      (node (ref "P1") (pin "C29") (pinfunction "C29_C29") (pintype "passive"))
      (node (ref "RT18") (pin "10") (pinfunction "10_10") (pintype "passive"))
    )
    (net (code "174") (name "Net-(P1-PadC30)") (class "Default")
      (node (ref "P1") (pin "C30") (pinfunction "C30_C30") (pintype "passive"))
      (node (ref "RT18") (pin "9") (pinfunction "9_9") (pintype "passive"))
    )
    (net (code "175") (name "VAuxN") (class "Default")
      (node (ref "P1") (pin "A31") (pinfunction "A31_A31") (pintype "passive"))
    )
    (net (code "176") (name "VAuxP") (class "Default")
      (node (ref "P1") (pin "C31") (pinfunction "C31_C31") (pintype "passive"))
    )
    (net (code "177") (name "VCC2V5") (class "Default")
      (node (ref "CT3") (pin "1") (pinfunction "1_1") (pintype "passive"))
      (node (ref "CT4") (pin "1") (pinfunction "1_1") (pintype "passive"))
      (node (ref "U27") (pin "18") (pinfunction "VccB_18") (pintype "power_in"))
      (node (ref "U27") (pin "7") (pinfunction "VccB_7") (pintype "power_in"))
    )
    (net (code "178") (name "VCC3V3") (class "Default")
      (node (ref "CT1") (pin "1") (pinfunction "1_1") (pintype "passive"))
      (node (ref "CT2") (pin "1") (pinfunction "1_1") (pintype "passive"))
      (node (ref "U27") (pin "31") (pinfunction "VccA_31") (pintype "power_in"))
      (node (ref "U27") (pin "42") (pinfunction "VccA_42") (pintype "power_in"))
    )
    (net (code "179") (name "unconnected-(P1-PadB31)") (class "Default")
      (node (ref "P1") (pin "B31") (pinfunction "B31_B31") (pintype "passive+no_connect"))
    )
    (net (code "180") (name "unconnected-(RT16-Pad6)") (class "Default")
      (node (ref "RT16") (pin "6") (pinfunction "6_6") (pintype "passive+no_connect"))
    )
    (net (code "181") (name "unconnected-(RT16-Pad7)") (class "Default")
      (node (ref "RT16") (pin "7") (pinfunction "7_7") (pintype "passive+no_connect"))
    )
    (net (code "182") (name "unconnected-(RT16-Pad8)") (class "Default")
      (node (ref "RT16") (pin "8") (pinfunction "8_8") (pintype "passive+no_connect"))
    )
    (net (code "183") (name "unconnected-(RT16-Pad9)") (class "Default")
      (node (ref "RT16") (pin "9") (pinfunction "9_9") (pintype "passive+no_connect"))
    )
    (net (code "184") (name "unconnected-(RT16-Pad10)") (class "Default")
      (node (ref "RT16") (pin "10") (pinfunction "10_10") (pintype "passive+no_connect"))
    )
    (net (code "185") (name "unconnected-(RT16-Pad11)") (class "Default")
      (node (ref "RT16") (pin "11") (pinfunction "11_11") (pintype "passive+no_connect"))
    )
    (net (code "186") (name "unconnected-(RT21-Pad1)") (class "Default")
      (node (ref "RT21") (pin "1") (pinfunction "1_1") (pintype "passive+no_connect"))
    )
    (net (code "187") (name "unconnected-(RT21-Pad16)") (class "Default")
      (node (ref "RT21") (pin "16") (pinfunction "16_16") (pintype "passive+no_connect"))
    )
  )
)
